# IMU_SCH.net
KiCad netlist of a schematic drawn in Altium Designer
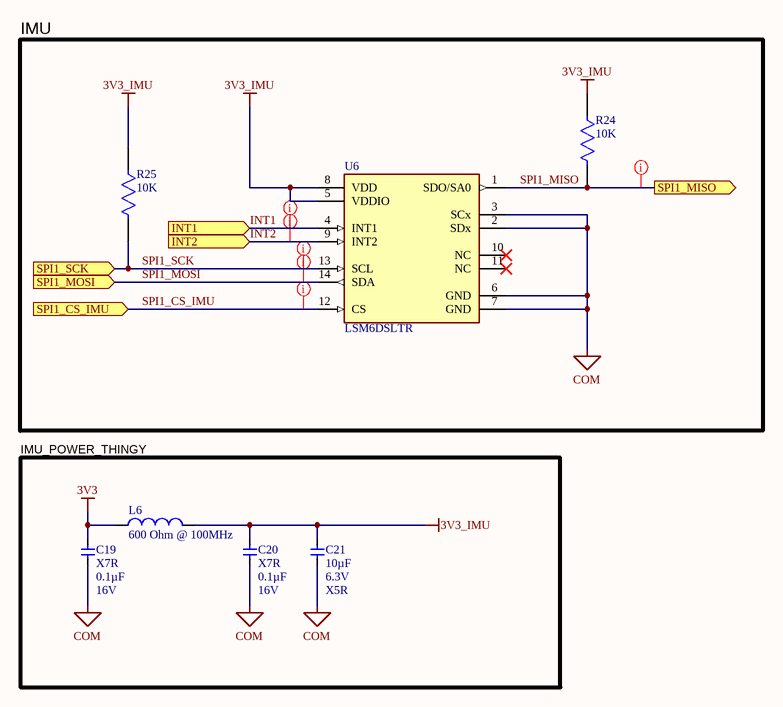
[diagram p0: IMU_SCH.SchDoc]

(export (version "E")
  (design (tool "Eeschema 10.0.6"))
  (components
    (comp (ref "C19")
      (value "GRM188R71C104KA01D")
      (footprint "C0603")
      (description "CAP CER 0.1UF 16V 10% X7R 0603")
      (fields
        (field (name "TOLERANCE") "±10%")
        (field (name "TEMPERATURE COEFFICIENT") "X7R")
        (field (name "CAPACITANCE") "0.1µF")
        (field (name "VOLTAGE - RATED") "16V")
      )
      (libsource (lib "Rockets_2015-2016") (part "GRM188R71C104KA01D"))
    )
    (comp (ref "C20")
      (value "GRM188R71C104KA01D")
      (footprint "C0603")
      (description "CAP CER 0.1UF 16V 10% X7R 0603")
      (fields
        (field (name "TOLERANCE") "±10%")
        (field (name "TEMPERATURE COEFFICIENT") "X7R")
        (field (name "CAPACITANCE") "0.1µF")
        (field (name "VOLTAGE - RATED") "16V")
      )
      (libsource (lib "Rockets_2015-2016") (part "GRM188R71C104KA01D"))
    )
    (comp (ref "C21")
      (value "GRM188R60J106ME47D")
      (footprint "C0603")
      (description "CAP CER 10UF 6.3V X5R 0603")
      (fields
        (field (name "MANUFACTURER") "Murata Electronics North America")
        (field (name "TOLERANCE") "±20%")
        (field (name "CAPACITANCE") "10µF")
        (field (name "VOLTAGE - RATED") "6.3V")
        (field (name "TEMPERATURE COEFFICIENT") "X5R")
      )
      (libsource (lib "Rockets_2015-2016") (part "GRM188R60J106ME47D"))
    )
    (comp (ref "L6")
      (value "MMZ1608B601C")
      (footprint "L0603")
      (description "FERRITE CHIP 600 OHM 500MA 0603")
      (fields (field (name "IMPEDANCE @ FREQUENCY") "600 Ohm @ 100MHz"))
      (libsource (lib "Rockets_2015-2016") (part "MMZ1608B601C"))
    )
    (comp (ref "R24")
      (value "10K")
      (footprint "FP-ERJ3G-IPC_C")
      (description "RES SMD 10K OHM 5% 1/10W 0603")
      (fields (field (name "TOLERANCE") "5%"))
      (libsource (lib "Altium Content Vault") (part "1029c3af85768c4190bb7ad29bc67b5"))
    )
    (comp (ref "R25")
      (value "10K")
      (footprint "FP-ERJ3G-IPC_C")
      (description "RES SMD 10K OHM 5% 1/10W 0603")
      (fields (field (name "TOLERANCE") "5%"))
      (libsource (lib "Altium Content Vault") (part "1029c3af85768c4190bb7ad29bc67b5"))
    )
    (comp (ref "U6")
      (value "LSM6DSLTR")
      (footprint "FP-LGA-14L-DM00249496-MFG")
      (description "IMU ACCEL/GYRO I2C/SPI 14LGA")
      (fields
        (field (name "MANUFACTURER") "STMicroelectronics")
        (field (name "OCTOPART") "https://octopart.com/lsm6dsltr-stmicroelectronics-66358193")
      )
      (libsource (lib "Altium Content Vault") (part "4e27e7d1829efda5344af1708d65448"))
    )
  )
  (nets
    (net (code "1") (name "/INT1") (class "Default")
      (node (ref "U6") (pin "4") (pinfunction "INT1_4") (pintype "input"))
    )
    (net (code "2") (name "/INT2") (class "Default")
      (node (ref "U6") (pin "9") (pinfunction "INT2_9") (pintype "input"))
    )
    (net (code "3") (name "/SPI1_CS_IMU") (class "Default")
      (node (ref "U6") (pin "12") (pinfunction "CS_12") (pintype "input"))
    )
    (net (code "4") (name "/SPI1_MISO") (class "Default")
      (node (ref "R24") (pin "2") (pinfunction "2_2") (pintype "passive"))
      (node (ref "U6") (pin "1") (pinfunction "SDO/SA0_1") (pintype "output"))
    )
    (net (code "5") (name "/SPI1_MOSI") (class "Default")
      (node (ref "U6") (pin "14") (pinfunction "SDA_14") (pintype "output"))
    )
    (net (code "6") (name "/SPI1_SCK") (class "Default")
      (node (ref "R25") (pin "2") (pinfunction "2_2") (pintype "passive"))
      (node (ref "U6") (pin "13") (pinfunction "SCL_13") (pintype "input"))
    )
    (net (code "7") (name "3V3") (class "Default")
      (node (ref "C19") (pin "2") (pinfunction "2_2") (pintype "passive"))
      (node (ref "L6") (pin "1") (pinfunction "1_1") (pintype "passive"))
    )
    (net (code "8") (name "3V3_IMU") (class "Default")
      (node (ref "C20") (pin "2") (pinfunction "2_2") (pintype "passive"))
      (node (ref "C21") (pin "2") (pinfunction "2_2") (pintype "passive"))
      (node (ref "L6") (pin "2") (pinfunction "2_2") (pintype "passive"))
      (node (ref "R24") (pin "1") (pinfunction "1_1") (pintype "passive"))
      (node (ref "R25") (pin "1") (pinfunction "1_1") (pintype "passive"))
      (node (ref "U6") (pin "5") (pinfunction "VDDIO_5") (pintype "power_in"))
      (node (ref "U6") (pin "8") (pinfunction "VDD_8") (pintype "power_in"))
    )
    (net (code "9") (name "COM") (class "Default")
      (node (ref "C19") (pin "1") (pinfunction "1_1") (pintype "passive"))
      (node (ref "C20") (pin "1") (pinfunction "1_1") (pintype "passive"))
      (node (ref "C21") (pin "1") (pinfunction "1_1") (pintype "passive"))
      (node (ref "U6") (pin "2") (pinfunction "SDx_2") (pintype "passive"))
      (node (ref "U6") (pin "3") (pinfunction "SCx_3") (pintype "passive"))
      (node (ref "U6") (pin "6") (pinfunction "GND_6") (pintype "power_in"))
      (node (ref "U6") (pin "7") (pinfunction "GND_7") (pintype "power_in"))
    )
    (net (code "10") (name "unconnected-(U6-NC-Pad10)") (class "Default")
      (node (ref "U6") (pin "10") (pinfunction "NC_10") (pintype "passive+no_connect"))
    )
    (net (code "11") (name "unconnected-(U6-NC-Pad11)") (class "Default")
      (node (ref "U6") (pin "11") (pinfunction "NC_11") (pintype "passive+no_connect"))
    )
  )
)
